# 4_-MCU_POWER.net
KiCad netlist of a schematic drawn in Altium Designer
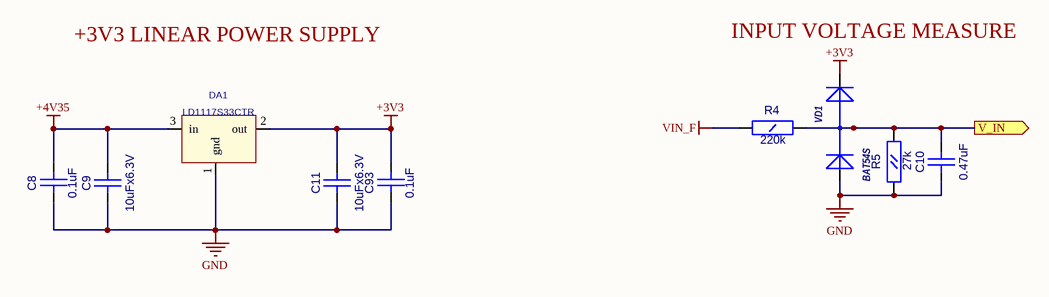
[diagram p0: [4]-MCU_POWER.SchDoc]

(export (version "E")
  (design (tool "Eeschema 10.0.6"))
  (components
    (comp (ref "C8")
      (value "0.1uF")
      (footprint "CC0603")
      (description "CC0603")
      (libsource (lib "gprs_modem_2") (part "CC0603"))
    )
    (comp (ref "C9")
      (value "10uFx6.3V")
      (footprint "CC0805")
      (description "CC0805")
      (libsource (lib "gprs_modem_2") (part "CC0805"))
    )
    (comp (ref "C10")
      (value "0.47uF")
      (footprint "CC0603")
      (description "CC0603")
      (libsource (lib "gprs_modem_2") (part "CC0603"))
    )
    (comp (ref "C11")
      (value "10uFx6.3V")
      (footprint "CC0805")
      (description "CC0805")
      (libsource (lib "gprs_modem_2") (part "CC0805"))
    )
    (comp (ref "C93")
      (value "0.1uF")
      (footprint "CC0603")
      (description "CC0603")
      (libsource (lib "gprs_modem_2") (part "CC0603"))
    )
    (comp (ref "DA1")
      (value "LD1117S33CTR")
      (footprint "SOT-223")
      (description "Linear Regulator 3.3V")
      (libsource (lib "fizik_lib") (part "NCP1117DT33RKG"))
    )
    (comp (ref "R4")
      (value "220k")
      (footprint "RC1206")
      (description "RC1206")
      (libsource (lib "fizik_lib") (part "RC1206"))
    )
    (comp (ref "R5")
      (value "27k")
      (footprint "RC0603")
      (description "RC0603")
      (libsource (lib "gprs_modem_2") (part "RC0603"))
    )
    (comp (ref "VD1")
      (value "BAT54S")
      (footprint "SOT-23(GSD)")
      (description "1.0 Ampere General Purpose Rectifier")
      (libsource (lib "gprs_modem_2") (part "BAT54S"))
    )
  )
  (nets
    (net (code "1") (name "+3V3") (class "Default")
      (node (ref "C11") (pin "2") (pinfunction "B_2") (pintype "passive"))
      (node (ref "C93") (pin "1") (pinfunction "A_1") (pintype "passive"))
      (node (ref "DA1") (pin "2") (pinfunction "out_2") (pintype "passive"))
      (node (ref "VD1") (pin "2") (pinfunction "K_2") (pintype "passive"))
    )
    (net (code "2") (name "+4V35") (class "Default")
      (node (ref "C8") (pin "1") (pinfunction "A_1") (pintype "passive"))
      (node (ref "C9") (pin "2") (pinfunction "B_2") (pintype "passive"))
      (node (ref "DA1") (pin "3") (pinfunction "in_3") (pintype "passive"))
    )
    (net (code "3") (name "/V_IN") (class "Default")
      (node (ref "C10") (pin "2") (pinfunction "B_2") (pintype "passive"))
      (node (ref "R4") (pin "2") (pinfunction "B_2") (pintype "passive"))
      (node (ref "R5") (pin "2") (pinfunction "B_2") (pintype "passive"))
      (node (ref "VD1") (pin "3") (pinfunction "AK_3") (pintype "passive"))
    )
    (net (code "4") (name "GND") (class "Default")
      (node (ref "C10") (pin "1") (pinfunction "A_1") (pintype "passive"))
      (node (ref "C11") (pin "1") (pinfunction "A_1") (pintype "passive"))
      (node (ref "C8") (pin "2") (pinfunction "B_2") (pintype "passive"))
      (node (ref "C9") (pin "1") (pinfunction "A_1") (pintype "passive"))
      (node (ref "C93") (pin "2") (pinfunction "B_2") (pintype "passive"))
      (node (ref "DA1") (pin "1") (pinfunction "gnd_1") (pintype "passive"))
      (node (ref "R5") (pin "1") (pinfunction "A_1") (pintype "passive"))
      (node (ref "VD1") (pin "1") (pinfunction "A_1") (pintype "passive"))
    )
    (net (code "5") (name "VIN_F") (class "Default")
      (node (ref "R4") (pin "1") (pinfunction "A_1") (pintype "passive"))
    )
  )
)
